# Solo_Edison.net
KiCad netlist of a schematic drawn in Altium Designer
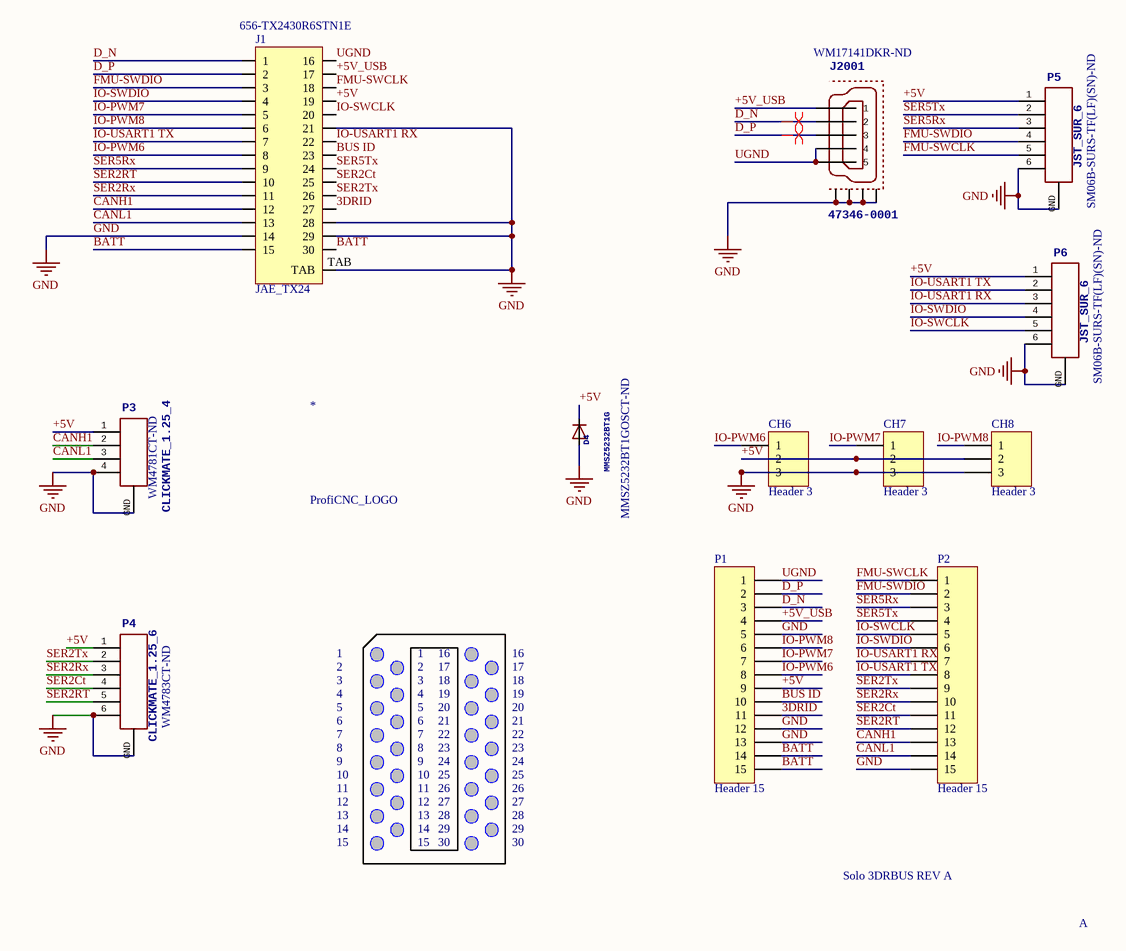
[diagram p0: Solo_Edison.SchDoc]

(export (version "E")
  (design (tool "Eeschema 10.0.6"))
  (components
    (comp (ref "*")
      (value "ProfiCNC_LOGO")
      (footprint "ProfiCNC_medium")
      (libsource (lib "ProfiCNC") (part "ProfiCNC_LOGO"))
    )
    (comp (ref "CH6")
      (value "Header 3")
      (footprint "HDR1X3")
      (description "Header, 3-Pin")
      (fields (field (name "PUBLISHER") "Altium Limited"))
      (libsource (lib "Miscellaneous Connectors") (part "Header 3"))
    )
    (comp (ref "CH7")
      (value "Header 3")
      (footprint "HDR1X3")
      (description "Header, 3-Pin")
      (fields (field (name "PUBLISHER") "Altium Limited"))
      (libsource (lib "Miscellaneous Connectors") (part "Header 3"))
    )
    (comp (ref "CH8")
      (value "Header 3")
      (footprint "HDR1X3")
      (description "Header, 3-Pin")
      (fields (field (name "PUBLISHER") "Altium Limited"))
      (libsource (lib "Miscellaneous Connectors") (part "Header 3"))
    )
    (comp (ref "D4")
      (value "MMSZ5232BT1G")
      (footprint "SOD-123")
      (description "DIODE ZENER 5.6V 500MW SOD123")
      (fields
        (field (name "SUPPLIER PART NUMBER 1") "MMSZ5232BT1GOSCT-ND")
        (field (name "3DR_PARTNO") "ECM0536")
      )
      (libsource (lib "adafruit") (part "DIODESOD-123"))
    )
    (comp (ref "J1")
      (value "JAE_TX24")
      (footprint "JAE TX24")
      (fields (field (name "SUPPLIER PART NUMBER 1") "656-TX2430R6STN1E"))
      (libsource (lib "3DR") (part "JAE_TX24"))
    )
    (comp (ref "J2001")
      (value "47346-0001")
      (footprint "MOLEX-47346-0001")
      (description "MICRO USB B, BOTTOM MOUNT")
      (fields
        (field (name "SUPPLIER PART NUMBER 1") "WM17141DKR-ND")
        (field (name "3DR_PARTNO") "ECM0486")
        (field (name "PARTNO") "0473460001")
      )
      (libsource (lib "pixhawk2") (part "MOLEX-47346-0001"))
    )
    (comp (ref "P1")
      (value "Header 15")
      (footprint "HDR1X15")
      (description "Header, 15-Pin")
      (fields (field (name "PUBLISHER") "Altium Limited"))
      (libsource (lib "") (part "Header 15_1"))
    )
    (comp (ref "P2")
      (value "Header 15")
      (footprint "HDR1X15")
      (description "Header, 15-Pin")
      (fields (field (name "PUBLISHER") "Altium Limited"))
      (libsource (lib "Miscellaneous Connectors") (part "Header 15"))
    )
    (comp (ref "P3")
      (value "CLICKMATE_1.25_4")
      (footprint "CLICKMATE_V4")
      (description "Connector, Rcpt, 4Pos, 1.25MM, W/B, VERT, SMD, Tin")
      (fields (field (name "SUPPLIER PART NUMBER 1") "WM4781CT-ND") (field (name "3DR_PARTNO") "PRT0441"))
      (libsource (lib "PCA_0005_FULL_CB_REV_A") (part "CLICKMATE_1.25_4"))
    )
    (comp (ref "P4")
      (value "CLICKMATE_1.25_6")
      (footprint "CLICKMATE_V6")
      (description "Connector, Rcpt, 6Pos, 1.25MM, W/B, VERT, SMD, Tin")
      (fields (field (name "SUPPLIER PART NUMBER 1") "WM4783CT-ND") (field (name "3DR_PARTNO") "PRT0439"))
      (libsource (lib "PCA_0005_FULL_CB_REV_A") (part "CLICKMATE_1.25_6"))
    )
    (comp (ref "P5")
      (value "JST_SUR_6")
      (footprint "JST_SUR_H6")
      (description "Connector, Header, 6Pos, .8mm IDC, R/A, SMD, Tin")
      (fields
        (field (name "SUPPLIER PART NUMBER 1") "SM06B-SURS-TF(LF)(SN)-ND")
        (field (name "3DR_PARTNO") "PRT0442")
      )
      (libsource (lib "PCA_0005_FULL_CB_REV_A") (part "JST_SUR_6"))
    )
    (comp (ref "P6")
      (value "JST_SUR_6")
      (footprint "JST_SUR_H6")
      (description "Connector, Header, 6Pos, .8mm IDC, R/A, SMD, Tin")
      (fields
        (field (name "SUPPLIER PART NUMBER 1") "SM06B-SURS-TF(LF)(SN)-ND")
        (field (name "3DR_PARTNO") "PRT0442")
      )
      (libsource (lib "PCA_0005_FULL_CB_REV_A") (part "JST_SUR_6"))
    )
  )
  (nets
    (net (code "1") (name "/+5V") (class "Default")
      (node (ref "CH6") (pin "2") (pinfunction "2_2") (pintype "passive"))
      (node (ref "CH7") (pin "2") (pinfunction "2_2") (pintype "passive"))
      (node (ref "CH8") (pin "2") (pinfunction "2_2") (pintype "passive"))
      (node (ref "D4") (pin "C") (pinfunction "C_C") (pintype "passive"))
      (node (ref "J1") (pin "19") (pinfunction "19_19") (pintype "passive"))
      (node (ref "P1") (pin "9") (pinfunction "9_9") (pintype "passive"))
      (node (ref "P3") (pin "1") (pinfunction "1_1") (pintype "passive"))
      (node (ref "P4") (pin "1") (pinfunction "1_1") (pintype "passive"))
      (node (ref "P5") (pin "1") (pinfunction "1_1") (pintype "passive"))
      (node (ref "P6") (pin "1") (pinfunction "1_1") (pintype "passive"))
    )
    (net (code "2") (name "/+5V_USB") (class "Default")
      (node (ref "J1") (pin "17") (pinfunction "17_17") (pintype "passive"))
      (node (ref "J2001") (pin "VBUS") (pinfunction "1_VBUS") (pintype "open_emitter"))
      (node (ref "P1") (pin "4") (pinfunction "4_4") (pintype "passive"))
    )
    (net (code "3") (name "/3DRID") (class "Default")
      (node (ref "J1") (pin "27") (pinfunction "27_27") (pintype "passive"))
      (node (ref "P1") (pin "11") (pinfunction "11_11") (pintype "passive"))
    )
    (net (code "4") (name "/BATT") (class "Default")
      (node (ref "J1") (pin "15") (pinfunction "15_15") (pintype "passive"))
      (node (ref "J1") (pin "30") (pinfunction "30_30") (pintype "passive"))
      (node (ref "P1") (pin "14") (pinfunction "14_14") (pintype "passive"))
      (node (ref "P1") (pin "15") (pinfunction "15_15") (pintype "passive"))
    )
    (net (code "5") (name "/BUS ID") (class "Default")
      (node (ref "J1") (pin "23") (pinfunction "23_23") (pintype "passive"))
      (node (ref "P1") (pin "10") (pinfunction "10_10") (pintype "passive"))
    )
    (net (code "6") (name "/CANH1") (class "Default")
      (node (ref "J1") (pin "12") (pinfunction "12_12") (pintype "passive"))
      (node (ref "P2") (pin "13") (pinfunction "13_13") (pintype "passive"))
      (node (ref "P3") (pin "2") (pinfunction "2_2") (pintype "passive"))
    )
    (net (code "7") (name "/CANL1") (class "Default")
      (node (ref "J1") (pin "13") (pinfunction "13_13") (pintype "passive"))
      (node (ref "P2") (pin "14") (pinfunction "14_14") (pintype "passive"))
      (node (ref "P3") (pin "3") (pinfunction "3_3") (pintype "passive"))
    )
    (net (code "8") (name "/D_N") (class "Default")
      (node (ref "J1") (pin "1") (pinfunction "1_1") (pintype "passive"))
      (node (ref "J2001") (pin "D-") (pinfunction "2_D-") (pintype "passive"))
      (node (ref "P1") (pin "3") (pinfunction "3_3") (pintype "passive"))
    )
    (net (code "9") (name "/D_P") (class "Default")
      (node (ref "J1") (pin "2") (pinfunction "2_2") (pintype "passive"))
      (node (ref "J2001") (pin "D+") (pinfunction "3_D+") (pintype "passive"))
      (node (ref "P1") (pin "2") (pinfunction "2_2") (pintype "passive"))
    )
    (net (code "10") (name "/FMU-SWCLK") (class "Default")
      (node (ref "J1") (pin "18") (pinfunction "18_18") (pintype "passive"))
      (node (ref "P2") (pin "1") (pinfunction "1_1") (pintype "passive"))
      (node (ref "P5") (pin "5") (pinfunction "5_5") (pintype "passive"))
    )
    (net (code "11") (name "/FMU-SWDIO") (class "Default")
      (node (ref "J1") (pin "3") (pinfunction "3_3") (pintype "passive"))
      (node (ref "P2") (pin "2") (pinfunction "2_2") (pintype "passive"))
      (node (ref "P5") (pin "4") (pinfunction "4_4") (pintype "passive"))
    )
    (net (code "12") (name "/IO-PWM6") (class "Default")
      (node (ref "CH6") (pin "1") (pinfunction "1_1") (pintype "passive"))
      (node (ref "J1") (pin "8") (pinfunction "8_8") (pintype "passive"))
      (node (ref "P1") (pin "8") (pinfunction "8_8") (pintype "passive"))
    )
    (net (code "13") (name "/IO-PWM7") (class "Default")
      (node (ref "CH7") (pin "1") (pinfunction "1_1") (pintype "passive"))
      (node (ref "J1") (pin "5") (pinfunction "5_5") (pintype "passive"))
      (node (ref "P1") (pin "7") (pinfunction "7_7") (pintype "passive"))
    )
    (net (code "14") (name "/IO-PWM8") (class "Default")
      (node (ref "CH8") (pin "1") (pinfunction "1_1") (pintype "passive"))
      (node (ref "J1") (pin "6") (pinfunction "6_6") (pintype "passive"))
      (node (ref "P1") (pin "6") (pinfunction "6_6") (pintype "passive"))
    )
    (net (code "15") (name "/IO-SWCLK") (class "Default")
      (node (ref "J1") (pin "20") (pinfunction "20_20") (pintype "passive"))
      (node (ref "P2") (pin "5") (pinfunction "5_5") (pintype "passive"))
      (node (ref "P6") (pin "5") (pinfunction "5_5") (pintype "passive"))
    )
    (net (code "16") (name "/IO-SWDIO") (class "Default")
      (node (ref "J1") (pin "4") (pinfunction "4_4") (pintype "passive"))
      (node (ref "P2") (pin "6") (pinfunction "6_6") (pintype "passive"))
      (node (ref "P6") (pin "4") (pinfunction "4_4") (pintype "passive"))
    )
    (net (code "17") (name "/IO-USART1 RX") (class "Default")
      (node (ref "J1") (pin "22") (pinfunction "22_22") (pintype "passive"))
      (node (ref "P2") (pin "7") (pinfunction "7_7") (pintype "passive"))
      (node (ref "P6") (pin "3") (pinfunction "3_3") (pintype "passive"))
    )
    (net (code "18") (name "/IO-USART1 TX") (class "Default")
      (node (ref "J1") (pin "7") (pinfunction "7_7") (pintype "passive"))
      (node (ref "P2") (pin "8") (pinfunction "8_8") (pintype "passive"))
      (node (ref "P6") (pin "2") (pinfunction "2_2") (pintype "passive"))
    )
    (net (code "19") (name "/SER2Ct") (class "Default")
      (node (ref "J1") (pin "25") (pinfunction "25_25") (pintype "passive"))
      (node (ref "P2") (pin "11") (pinfunction "11_11") (pintype "passive"))
      (node (ref "P4") (pin "4") (pinfunction "4_4") (pintype "passive"))
    )
    (net (code "20") (name "/SER2RT") (class "Default")
      (node (ref "J1") (pin "10") (pinfunction "10_10") (pintype "passive"))
      (node (ref "P2") (pin "12") (pinfunction "12_12") (pintype "passive"))
      (node (ref "P4") (pin "5") (pinfunction "5_5") (pintype "passive"))
    )
    (net (code "21") (name "/SER2Rx") (class "Default")
      (node (ref "J1") (pin "11") (pinfunction "11_11") (pintype "passive"))
      (node (ref "P2") (pin "10") (pinfunction "10_10") (pintype "passive"))
      (node (ref "P4") (pin "3") (pinfunction "3_3") (pintype "passive"))
    )
    (net (code "22") (name "/SER2Tx") (class "Default")
      (node (ref "J1") (pin "26") (pinfunction "26_26") (pintype "passive"))
      (node (ref "P2") (pin "9") (pinfunction "9_9") (pintype "passive"))
      (node (ref "P4") (pin "2") (pinfunction "2_2") (pintype "passive"))
    )
    (net (code "23") (name "/SER5Rx") (class "Default")
      (node (ref "J1") (pin "9") (pinfunction "9_9") (pintype "passive"))
      (node (ref "P2") (pin "3") (pinfunction "3_3") (pintype "passive"))
      (node (ref "P5") (pin "3") (pinfunction "3_3") (pintype "passive"))
    )
    (net (code "24") (name "/SER5Tx") (class "Default")
      (node (ref "J1") (pin "24") (pinfunction "24_24") (pintype "passive"))
      (node (ref "P2") (pin "4") (pinfunction "4_4") (pintype "passive"))
      (node (ref "P5") (pin "2") (pinfunction "2_2") (pintype "passive"))
    )
    (net (code "25") (name "/UGND") (class "Default")
      (node (ref "J1") (pin "16") (pinfunction "16_16") (pintype "passive"))
      (node (ref "J2001") (pin "GND") (pinfunction "5_GND") (pintype "open_emitter"))
      (node (ref "J2001") (pin "ID") (pinfunction "4_ID") (pintype "passive"))
      (node (ref "P1") (pin "1") (pinfunction "1_1") (pintype "passive"))
    )
    (net (code "26") (name "GND") (class "Default")
      (node (ref "CH6") (pin "3") (pinfunction "3_3") (pintype "passive"))
      (node (ref "CH7") (pin "3") (pinfunction "3_3") (pintype "passive"))
      (node (ref "CH8") (pin "3") (pinfunction "3_3") (pintype "passive"))
      (node (ref "D4") (pin "A") (pinfunction "A_A") (pintype "passive"))
      (node (ref "J1") (pin "14") (pinfunction "14_14") (pintype "passive"))
      (node (ref "J1") (pin "21") (pinfunction "21_21") (pintype "passive"))
      (node (ref "J1") (pin "28") (pinfunction "28_28") (pintype "passive"))
      (node (ref "J1") (pin "29") (pinfunction "29_29") (pintype "passive"))
      (node (ref "J1") (pin "TAB") (pinfunction "TAB_TAB") (pintype "passive"))
      (node (ref "J2001") (pin "GND1") (pinfunction "GND1_GND1") (pintype "passive"))
      (node (ref "J2001") (pin "GND2") (pinfunction "GND2_GND2") (pintype "passive"))
      (node (ref "J2001") (pin "GND3") (pinfunction "GND3_GND3") (pintype "passive"))
      (node (ref "J2001") (pin "GND4") (pinfunction "GND4_GND4") (pintype "passive"))
      (node (ref "P1") (pin "12") (pinfunction "12_12") (pintype "passive"))
      (node (ref "P1") (pin "13") (pinfunction "13_13") (pintype "passive"))
      (node (ref "P1") (pin "5") (pinfunction "5_5") (pintype "passive"))
      (node (ref "P2") (pin "15") (pinfunction "15_15") (pintype "passive"))
      (node (ref "P3") (pin "4") (pinfunction "4_4") (pintype "passive"))
      (node (ref "P3") (pin "GND") (pinfunction "GND_GND") (pintype "passive"))
      (node (ref "P4") (pin "6") (pinfunction "6_6") (pintype "passive"))
      (node (ref "P4") (pin "GND") (pinfunction "GND_GND") (pintype "passive"))
      (node (ref "P5") (pin "6") (pinfunction "6_6") (pintype "passive"))
      (node (ref "P5") (pin "GND") (pinfunction "GND_GND") (pintype "passive"))
      (node (ref "P6") (pin "6") (pinfunction "6_6") (pintype "passive"))
      (node (ref "P6") (pin "GND") (pinfunction "GND_GND") (pintype "passive"))
    )
  )
)
